# v1_0.net
KiCad netlist of a schematic drawn in Altium Designer
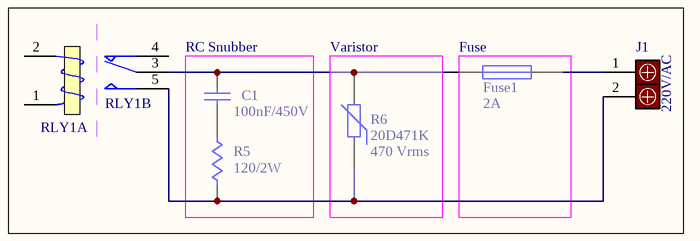
[diagram p0: v1.0.SchDoc]

(export (version "E")
  (design (tool "Eeschema 10.0.6"))
  (components
    (comp (ref "C1")
      (value "100nF/450V")
      (footprint "C_THD_CER_(P2.54-D3.5-T1.5)")
      (description "Capacitor, Ceramic Multilayer")
      (libsource (lib "Passive") (part "Capacitor_Ceramic"))
    )
    (comp (ref "Fuse1")
      (value "2A")
      (footprint "PIN-W2/E2.8")
      (description "Fuse")
      (fields (field (name "MANUFACTURER") "Generic Components") (field (name "PUBLISHER") "Altium Limited"))
      (libsource (lib "Miscellaneous Devices") (part "Fuse 1"))
    )
    (comp (ref "J1")
      (value "2PIN")
      (footprint "Connector_Phoenix_2PIN_MSTB")
      (description "Connector, Header, 2Pin")
      (libsource (lib "Connector") (part "Connector1x2_Power"))
    )
    (comp (ref "R5")
      (value "120/2W")
      (footprint "R_THD_AXIAL0.9(3W)")
      (description "Resistor")
      (libsource (lib "Passive") (part "Resistor_3Form"))
    )
    (comp (ref "R6")
      (value "20D471K")
      (description "Varistor")
      (fields
        (field (name "MANUFACTURER") "Generic Components")
        (field (name "TEXT") "470 Vrms")
        (field (name "PUBLISHER") "Altium Limited")
      )
      (libsource (lib "Miscellaneous Devices") (part "Res Varistor"))
    )
    (comp (ref "RLY1")
      (value "12V")
      (footprint "RELAY_SPDT_5PIN_2216")
      (description "SPDT Relay")
      (libsource (lib "Passive") (part "Relay_SPDT_2Form"))
    )
  )
  (nets
    (net (code "1") (name "Net-(C1-Pad1)") (class "Default")
      (node (ref "C1") (pin "1") (pinfunction "1_1") (pintype "passive"))
      (node (ref "R5") (pin "2") (pinfunction "2_2") (pintype "passive"))
    )
    (net (code "2") (name "Net-(Fuse1-Pad2)") (class "Default")
      (node (ref "Fuse1") (pin "2") (pinfunction "2_2") (pintype "passive"))
      (node (ref "J1") (pin "1") (pinfunction "1_1") (pintype "passive"))
    )
    (net (code "3") (name "Net-(RLY1B-COM)") (class "Default")
      (node (ref "C1") (pin "2") (pinfunction "2_2") (pintype "passive"))
      (node (ref "Fuse1") (pin "1") (pinfunction "1_1") (pintype "passive"))
      (node (ref "R6") (pin "2") (pinfunction "2_2") (pintype "passive"))
      (node (ref "RLY1") (pin "3") (pinfunction "COM_3") (pintype "passive"))
    )
    (net (code "4") (name "Net-(RLY1B-NO)") (class "Default")
      (node (ref "J1") (pin "2") (pinfunction "2_2") (pintype "passive"))
      (node (ref "R5") (pin "1") (pinfunction "1_1") (pintype "passive"))
      (node (ref "R6") (pin "1") (pinfunction "1_1") (pintype "passive"))
      (node (ref "RLY1") (pin "5") (pinfunction "NO_5") (pintype "passive"))
    )
    (net (code "5") (name "unconnected-(RLY1A-T1-Pad2)") (class "Default")
      (node (ref "RLY1") (pin "2") (pinfunction "T1_2") (pintype "passive"))
    )
    (net (code "6") (name "unconnected-(RLY1A-T2-Pad1)") (class "Default")
      (node (ref "RLY1") (pin "1") (pinfunction "T2_1") (pintype "passive"))
    )
    (net (code "7") (name "unconnected-(RLY1B-NC-Pad4)") (class "Default")
      (node (ref "RLY1") (pin "4") (pinfunction "NC_4") (pintype "passive"))
    )
  )
)
